# VIDEO_OUT_SVGA.net
KiCad netlist of a schematic drawn in Altium Designer
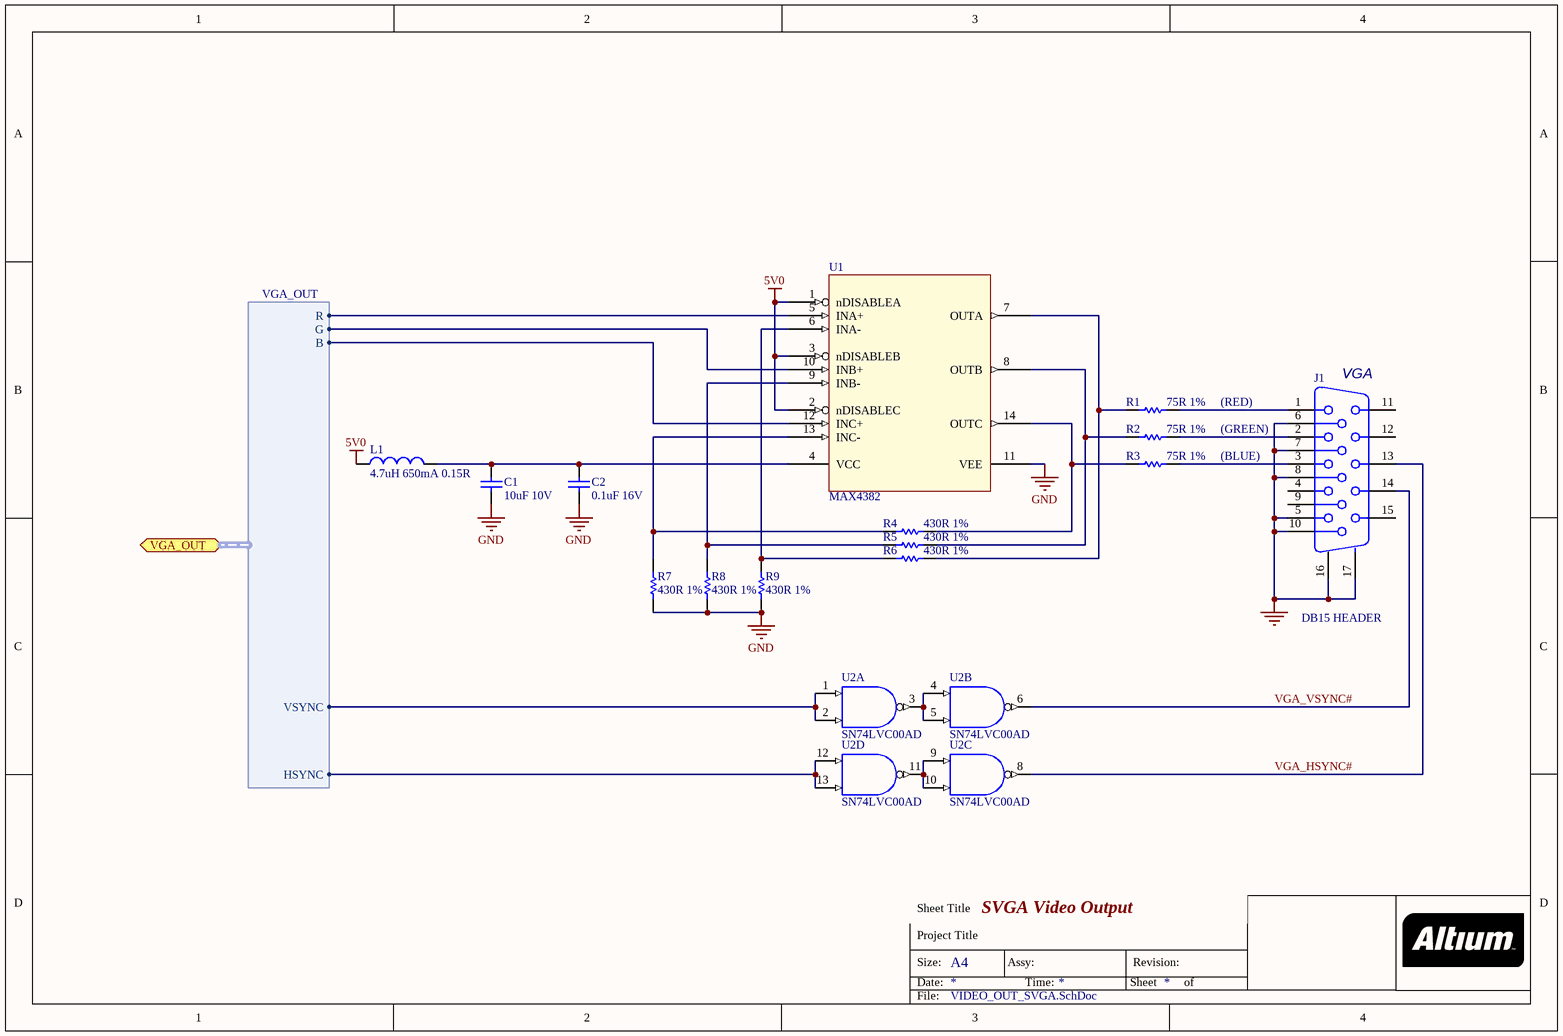
[diagram p0: VIDEO_OUT_SVGA.SchDoc]

(export (version "E")
  (design (tool "Eeschema 10.0.6"))
  (components
    (comp (ref "C1")
      (value "10uF 10V")
      (footprint "CAPC2012-STAR")
      (description "Capacitor, Ceramic, 10uF 10% 10V 0805 (2012) X5R")
      (fields (field (name "TOLERANCE") "10 %"))
      (libsource (lib "AltiumDesignLibrary") (part "CAP-NP"))
    )
    (comp (ref "C2")
      (value "0.1uF 16V")
      (footprint "CAPC1005-STAR")
      (description "Capacitor, Ceramic, 0.1uF 10% 16V 0402 (1005) X7R")
      (fields (field (name "TOLERANCE") "10 %"))
      (libsource (lib "AltiumDesignLibrary") (part "CAP-NP"))
    )
    (comp (ref "J1")
      (value "DB15 HEADER")
      (footprint "DB15-VGA-Female")
      (description "Connector, DB15 Right-Angle Female (Analog RGB Video)/Blue")
      (libsource (lib "AltiumDesignLibrary") (part "CON-DB-15-F-RA"))
    )
    (comp (ref "L1")
      (value "4.7uH 650mA 0.15R")
      (footprint "INDC3225")
      (description "Inductor, 4.7uH 650mA 0.15R 1210 (3225) LQH32CN4R7M11L")
      (libsource (lib "AltiumDesignLibrary") (part "IND"))
    )
    (comp (ref "R1")
      (value "75R 1%")
      (footprint "RESC1005-STAR")
      (description "Resistor, 75R 1% 0402")
      (fields (field (name "TOLERANCE") "1 %"))
      (libsource (lib "AltiumDesignLibrary") (part "RES"))
    )
    (comp (ref "R2")
      (value "75R 1%")
      (footprint "RESC1005-STAR")
      (description "Resistor, 75R 1% 0402")
      (fields (field (name "TOLERANCE") "1 %"))
      (libsource (lib "AltiumDesignLibrary") (part "RES"))
    )
    (comp (ref "R3")
      (value "75R 1%")
      (footprint "RESC1005-STAR")
      (description "Resistor, 75R 1% 0402")
      (fields (field (name "TOLERANCE") "1 %"))
      (libsource (lib "AltiumDesignLibrary") (part "RES"))
    )
    (comp (ref "R4")
      (value "430R 1%")
      (footprint "RESC1005-STAR")
      (description "Resistor, 430R 1% 0402 (1005)")
      (fields (field (name "TOLERANCE") "1 %"))
      (libsource (lib "AltiumDesignLibrary") (part "RES"))
    )
    (comp (ref "R5")
      (value "430R 1%")
      (footprint "RESC1005-STAR")
      (description "Resistor, 430R 1% 0402 (1005)")
      (fields (field (name "TOLERANCE") "1 %"))
      (libsource (lib "AltiumDesignLibrary") (part "RES"))
    )
    (comp (ref "R6")
      (value "430R 1%")
      (footprint "RESC1005-STAR")
      (description "Resistor, 430R 1% 0402 (1005)")
      (fields (field (name "TOLERANCE") "1 %"))
      (libsource (lib "AltiumDesignLibrary") (part "RES"))
    )
    (comp (ref "R7")
      (value "430R 1%")
      (footprint "RESC1005-STAR")
      (description "Resistor, 430R 1% 0402 (1005)")
      (fields (field (name "TOLERANCE") "1 %"))
      (libsource (lib "AltiumDesignLibrary") (part "RES"))
    )
    (comp (ref "R8")
      (value "430R 1%")
      (footprint "RESC1005-STAR")
      (description "Resistor, 430R 1% 0402 (1005)")
      (fields (field (name "TOLERANCE") "1 %"))
      (libsource (lib "AltiumDesignLibrary") (part "RES"))
    )
    (comp (ref "R9")
      (value "430R 1%")
      (footprint "RESC1005-STAR")
      (description "Resistor, 430R 1% 0402 (1005)")
      (fields (field (name "TOLERANCE") "1 %"))
      (libsource (lib "AltiumDesignLibrary") (part "RES"))
    )
    (comp (ref "U1")
      (value "MAX4382")
      (footprint "TSSOP-14")
      (description "MAX4382 OPAMP, TSSOP14")
      (libsource (lib "AltiumDesignLibrary") (part "MAX4382"))
    )
    (comp (ref "U2")
      (value "SN74LVC00AD")
      (footprint "SOIC127P600-14")
      (description "SN74LVC00AD, Quad 2-Input Positive-Nand Gates, 1.65-3.6V, 5V Tolerant Inputs")
      (libsource (lib "AltiumDesignLibrary") (part "SN74LVC00AD"))
    )
  )
  (nets
    (net (code "2") (name "/B") (class "Default")
      (node (ref "U1") (pin "12") (pinfunction "INC+_12") (pintype "input"))
    )
    (net (code "3") (name "/G") (class "Default")
      (node (ref "U1") (pin "10") (pinfunction "INB+_10") (pintype "input"))
    )
    (net (code "4") (name "/HSYNC") (class "Default")
      (node (ref "U2") (pin "12") (pinfunction "A_12") (pintype "input"))
      (node (ref "U2") (pin "13") (pinfunction "B_13") (pintype "input"))
    )
    (net (code "5") (name "/R") (class "Default")
      (node (ref "U1") (pin "5") (pinfunction "INA+_5") (pintype "input"))
    )
    (net (code "6") (name "/VGA_HSYNC#") (class "Default")
      (node (ref "J1") (pin "13") (pinfunction "13_13") (pintype "passive"))
      (node (ref "U2") (pin "8") (pinfunction "Y_8") (pintype "output"))
    )
    (net (code "7") (name "/VGA_VSYNC#") (class "Default")
      (node (ref "J1") (pin "14") (pinfunction "14_14") (pintype "passive"))
      (node (ref "U2") (pin "6") (pinfunction "Y_6") (pintype "output"))
    )
    (net (code "8") (name "/VSYNC") (class "Default")
      (node (ref "U2") (pin "1") (pinfunction "A_1") (pintype "input"))
      (node (ref "U2") (pin "2") (pinfunction "B_2") (pintype "input"))
    )
    (net (code "10") (name "5V0") (class "Default")
      (node (ref "L1") (pin "2") (pinfunction "2_2") (pintype "passive"))
      (node (ref "U1") (pin "1") (pinfunction "nDISABLEA_1") (pintype "input"))
      (node (ref "U1") (pin "2") (pinfunction "nDISABLEC_2") (pintype "input"))
      (node (ref "U1") (pin "3") (pinfunction "nDISABLEB_3") (pintype "input"))
    )
    (net (code "11") (name "GND") (class "Default")
      (node (ref "C1") (pin "1") (pinfunction "1_1") (pintype "passive"))
      (node (ref "C2") (pin "2") (pinfunction "2_2") (pintype "passive"))
      (node (ref "J1") (pin "10") (pinfunction "10_10") (pintype "power_in"))
      (node (ref "J1") (pin "16") (pinfunction "MH1_16") (pintype "passive"))
      (node (ref "J1") (pin "17") (pinfunction "MH2_17") (pintype "passive"))
      (node (ref "J1") (pin "5") (pinfunction "5_5") (pintype "power_in"))
      (node (ref "J1") (pin "6") (pinfunction "6_6") (pintype "power_in"))
      (node (ref "J1") (pin "7") (pinfunction "7_7") (pintype "power_in"))
      (node (ref "J1") (pin "8") (pinfunction "8_8") (pintype "power_in"))
      (node (ref "R7") (pin "1") (pinfunction "1_1") (pintype "passive"))
      (node (ref "R8") (pin "1") (pinfunction "1_1") (pintype "passive"))
      (node (ref "R9") (pin "1") (pinfunction "1_1") (pintype "passive"))
      (node (ref "U1") (pin "11") (pinfunction "VEE_11") (pintype "power_in"))
      (node (ref "U2") (pin "7") (pinfunction "GND_7") (pintype "power_in"))
    )
    (net (code "12") (name "Net-(J1-Pad1)") (class "Default")
      (node (ref "J1") (pin "1") (pinfunction "1_1") (pintype "passive"))
      (node (ref "R1") (pin "2") (pinfunction "2_2") (pintype "passive"))
    )
    (net (code "13") (name "Net-(J1-Pad2)") (class "Default")
      (node (ref "J1") (pin "2") (pinfunction "2_2") (pintype "passive"))
      (node (ref "R2") (pin "2") (pinfunction "2_2") (pintype "passive"))
    )
    (net (code "14") (name "Net-(J1-Pad3)") (class "Default")
      (node (ref "J1") (pin "3") (pinfunction "3_3") (pintype "passive"))
      (node (ref "R3") (pin "2") (pinfunction "2_2") (pintype "passive"))
    )
    (net (code "15") (name "Net-(U1-INA-)") (class "Default")
      (node (ref "R6") (pin "1") (pinfunction "1_1") (pintype "passive"))
      (node (ref "R9") (pin "2") (pinfunction "2_2") (pintype "passive"))
      (node (ref "U1") (pin "6") (pinfunction "INA-_6") (pintype "input"))
    )
    (net (code "16") (name "Net-(U1-INB-)") (class "Default")
      (node (ref "R5") (pin "1") (pinfunction "1_1") (pintype "passive"))
      (node (ref "R8") (pin "2") (pinfunction "2_2") (pintype "passive"))
      (node (ref "U1") (pin "9") (pinfunction "INB-_9") (pintype "input"))
    )
    (net (code "17") (name "Net-(U1-INC-)") (class "Default")
      (node (ref "R4") (pin "1") (pinfunction "1_1") (pintype "passive"))
      (node (ref "R7") (pin "2") (pinfunction "2_2") (pintype "passive"))
      (node (ref "U1") (pin "13") (pinfunction "INC-_13") (pintype "input"))
    )
    (net (code "18") (name "Net-(U1-OUTA)") (class "Default")
      (node (ref "R1") (pin "1") (pinfunction "1_1") (pintype "passive"))
      (node (ref "R6") (pin "2") (pinfunction "2_2") (pintype "passive"))
      (node (ref "U1") (pin "7") (pinfunction "OUTA_7") (pintype "output"))
    )
    (net (code "19") (name "Net-(U1-OUTB)") (class "Default")
      (node (ref "R2") (pin "1") (pinfunction "1_1") (pintype "passive"))
      (node (ref "R5") (pin "2") (pinfunction "2_2") (pintype "passive"))
      (node (ref "U1") (pin "8") (pinfunction "OUTB_8") (pintype "output"))
    )
    (net (code "20") (name "Net-(U1-OUTC)") (class "Default")
      (node (ref "R3") (pin "1") (pinfunction "1_1") (pintype "passive"))
      (node (ref "R4") (pin "2") (pinfunction "2_2") (pintype "passive"))
      (node (ref "U1") (pin "14") (pinfunction "OUTC_14") (pintype "output"))
    )
    (net (code "21") (name "Net-(U1-VCC)") (class "Default")
      (node (ref "C1") (pin "2") (pinfunction "2_2") (pintype "passive"))
      (node (ref "C2") (pin "1") (pinfunction "1_1") (pintype "passive"))
      (node (ref "L1") (pin "1") (pinfunction "1_1") (pintype "passive"))
      (node (ref "U1") (pin "4") (pinfunction "VCC_4") (pintype "power_in"))
    )
    (net (code "22") (name "Net-(U2A-Y)") (class "Default")
      (node (ref "U2") (pin "3") (pinfunction "Y_3") (pintype "output"))
      (node (ref "U2") (pin "4") (pinfunction "A_4") (pintype "input"))
      (node (ref "U2") (pin "5") (pinfunction "B_5") (pintype "input"))
    )
    (net (code "23") (name "Net-(U2C-A)") (class "Default")
      (node (ref "U2") (pin "10") (pinfunction "B_10") (pintype "input"))
      (node (ref "U2") (pin "11") (pinfunction "Y_11") (pintype "output"))
      (node (ref "U2") (pin "9") (pinfunction "A_9") (pintype "input"))
    )
    (net (code "24") (name "VDD") (class "Default")
      (node (ref "U2") (pin "14") (pinfunction "VDD_14") (pintype "power_in"))
    )
    (net (code "25") (name "unconnected-(J1-Pad4)") (class "Default")
      (node (ref "J1") (pin "4") (pinfunction "4_4") (pintype "passive"))
    )
    (net (code "26") (name "unconnected-(J1-Pad9)") (class "Default")
      (node (ref "J1") (pin "9") (pinfunction "9_9") (pintype "passive"))
    )
    (net (code "27") (name "unconnected-(J1-Pad11)") (class "Default")
      (node (ref "J1") (pin "11") (pinfunction "11_11") (pintype "power_in"))
    )
    (net (code "28") (name "unconnected-(J1-Pad12)") (class "Default")
      (node (ref "J1") (pin "12") (pinfunction "12_12") (pintype "passive"))
    )
    (net (code "29") (name "unconnected-(J1-Pad15)") (class "Default")
      (node (ref "J1") (pin "15") (pinfunction "15_15") (pintype "passive"))
    )
  )
)
